# Puzzle_4-Digit_Display_V1_0.net
KiCad netlist of a schematic drawn in EAGLE
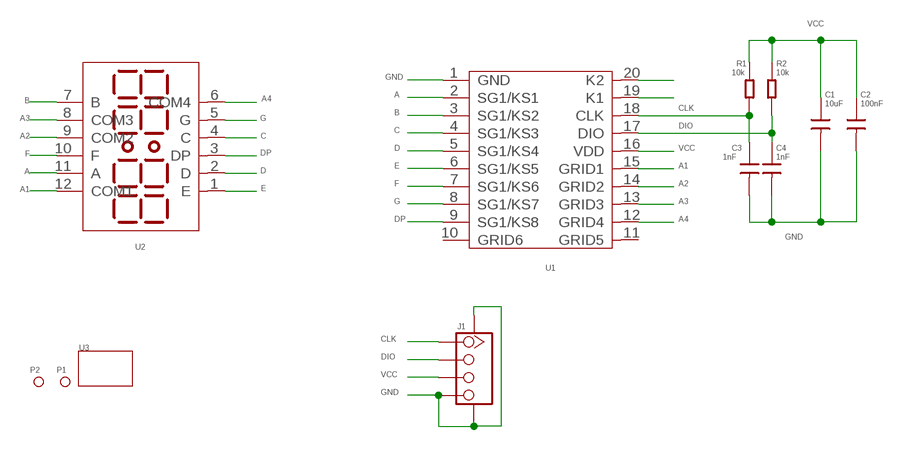
[diagram p0: schematic, sheet 1]

(export (version "E")
  (design (tool "Eeschema 10.0.6"))
  (components
    (comp (ref "C1")
      (value "10uF")
      (footprint "eagle-import:0603")
      (libsource (lib "eagle-import") (part "C-0603"))
    )
    (comp (ref "C2")
      (value "100nF")
      (footprint "eagle-import:0603")
      (libsource (lib "eagle-import") (part "C-0603"))
    )
    (comp (ref "C3")
      (value "1nF")
      (footprint "eagle-import:0603")
      (libsource (lib "eagle-import") (part "C-0603"))
    )
    (comp (ref "C4")
      (value "1nF")
      (footprint "eagle-import:0603")
      (libsource (lib "eagle-import") (part "C-0603"))
    )
    (comp (ref "J1")
      (value "TWIG-4P-2.0-SMD-FEMALE-REINFORCE'90D'")
      (footprint "eagle-import:4P-SMD-2.0-90D")
      (libsource (lib "eagle-import") (part "TWIG-4P-2.0-SMD-FEMALE-REINFORCE'90D'"))
    )
    (comp (ref "P1")
      (value "PAD-MARK")
      (footprint "eagle-import:ROUND-MARK-0.635")
      (libsource (lib "eagle-import") (part "PAD-MARK"))
    )
    (comp (ref "P2")
      (value "PAD-MARK")
      (footprint "eagle-import:ROUND-MARK-0.635")
      (libsource (lib "eagle-import") (part "PAD-MARK"))
    )
    (comp (ref "R1")
      (value "10k")
      (footprint "eagle-import:0603")
      (libsource (lib "eagle-import") (part "R-0603"))
    )
    (comp (ref "R2")
      (value "10k")
      (footprint "eagle-import:0603")
      (libsource (lib "eagle-import") (part "R-0603"))
    )
    (comp (ref "U1")
      (value "TM1637")
      (footprint "eagle-import:SOP20-10.45")
      (libsource (lib "eagle-import") (part "TM1637"))
    )
    (comp (ref "U2")
      (value "LED-4-BETY-7-SEG")
      (footprint "eagle-import:7-4-BYTE-SEG-2.54-30X14X7.3H")
      (libsource (lib "eagle-import") (part "LED-4-BETY-7-SEG"))
    )
    (comp (ref "U3")
      (value "TWIG-2U")
      (footprint "eagle-import:2U-DIM-W_-DRILL")
      (libsource (lib "eagle-import") (part "TWIG-2U"))
    )
  )
  (nets
    (net (code "1") (name "/A") (class "Default")
      (node (ref "U1") (pin "2") (pinfunction "SG1/KS1_2") (pintype "bidirectional"))
      (node (ref "U2") (pin "11") (pinfunction "A_11") (pintype "bidirectional"))
    )
    (net (code "2") (name "/A1") (class "Default")
      (node (ref "U1") (pin "15") (pinfunction "GRID1_15") (pintype "bidirectional"))
      (node (ref "U2") (pin "12") (pinfunction "COM1_12") (pintype "bidirectional"))
    )
    (net (code "3") (name "/A2") (class "Default")
      (node (ref "U1") (pin "14") (pinfunction "GRID2_14") (pintype "bidirectional"))
      (node (ref "U2") (pin "9") (pinfunction "COM2_9") (pintype "bidirectional"))
    )
    (net (code "4") (name "/A3") (class "Default")
      (node (ref "U1") (pin "13") (pinfunction "GRID3_13") (pintype "bidirectional"))
      (node (ref "U2") (pin "8") (pinfunction "COM3_8") (pintype "bidirectional"))
    )
    (net (code "5") (name "/A4") (class "Default")
      (node (ref "U1") (pin "12") (pinfunction "GRID4_12") (pintype "bidirectional"))
      (node (ref "U2") (pin "6") (pinfunction "COM4_6") (pintype "bidirectional"))
    )
    (net (code "6") (name "/B") (class "Default")
      (node (ref "U1") (pin "3") (pinfunction "SG1/KS2_3") (pintype "bidirectional"))
      (node (ref "U2") (pin "7") (pinfunction "B_7") (pintype "bidirectional"))
    )
    (net (code "7") (name "/C") (class "Default")
      (node (ref "U1") (pin "4") (pinfunction "SG1/KS3_4") (pintype "bidirectional"))
      (node (ref "U2") (pin "4") (pinfunction "C_4") (pintype "bidirectional"))
    )
    (net (code "8") (name "/CLK") (class "Default")
      (node (ref "C3") (pin "1") (pinfunction "1_1") (pintype "passive"))
      (node (ref "J1") (pin "1") (pinfunction "1_1") (pintype "bidirectional"))
      (node (ref "R1") (pin "2") (pinfunction "2_2") (pintype "passive"))
      (node (ref "U1") (pin "18") (pinfunction "CLK_18") (pintype "bidirectional"))
    )
    (net (code "9") (name "/D") (class "Default")
      (node (ref "U1") (pin "5") (pinfunction "SG1/KS4_5") (pintype "bidirectional"))
      (node (ref "U2") (pin "2") (pinfunction "D_2") (pintype "bidirectional"))
    )
    (net (code "10") (name "/DIO") (class "Default")
      (node (ref "C4") (pin "1") (pinfunction "1_1") (pintype "passive"))
      (node (ref "J1") (pin "2") (pinfunction "2_2") (pintype "bidirectional"))
      (node (ref "R2") (pin "2") (pinfunction "2_2") (pintype "passive"))
      (node (ref "U1") (pin "17") (pinfunction "DIO_17") (pintype "bidirectional"))
    )
    (net (code "11") (name "/DP") (class "Default")
      (node (ref "U1") (pin "9") (pinfunction "SG1/KS8_9") (pintype "bidirectional"))
      (node (ref "U2") (pin "3") (pinfunction "DP_3") (pintype "bidirectional"))
    )
    (net (code "12") (name "/E") (class "Default")
      (node (ref "U1") (pin "6") (pinfunction "SG1/KS5_6") (pintype "bidirectional"))
      (node (ref "U2") (pin "1") (pinfunction "E_1") (pintype "bidirectional"))
    )
    (net (code "13") (name "/F") (class "Default")
      (node (ref "U1") (pin "7") (pinfunction "SG1/KS6_7") (pintype "bidirectional"))
      (node (ref "U2") (pin "10") (pinfunction "F_10") (pintype "bidirectional"))
    )
    (net (code "14") (name "/G") (class "Default")
      (node (ref "U1") (pin "8") (pinfunction "SG1/KS7_8") (pintype "bidirectional"))
      (node (ref "U2") (pin "5") (pinfunction "G_5") (pintype "bidirectional"))
    )
    (net (code "15") (name "/GND") (class "Default")
      (node (ref "C1") (pin "2") (pinfunction "2_2") (pintype "passive"))
      (node (ref "C2") (pin "2") (pinfunction "2_2") (pintype "passive"))
      (node (ref "C3") (pin "2") (pinfunction "2_2") (pintype "passive"))
      (node (ref "C4") (pin "2") (pinfunction "2_2") (pintype "passive"))
      (node (ref "J1") (pin "4") (pinfunction "4_4") (pintype "bidirectional"))
      (node (ref "J1") (pin "SS1") (pinfunction "SS1_SS1") (pintype "bidirectional"))
      (node (ref "J1") (pin "SS2") (pinfunction "SS2_SS2") (pintype "bidirectional"))
      (node (ref "U1") (pin "1") (pinfunction "GND_1") (pintype "bidirectional"))
    )
    (net (code "16") (name "/VCC") (class "Default")
      (node (ref "C1") (pin "1") (pinfunction "1_1") (pintype "passive"))
      (node (ref "C2") (pin "1") (pinfunction "1_1") (pintype "passive"))
      (node (ref "J1") (pin "3") (pinfunction "3_3") (pintype "bidirectional"))
      (node (ref "R1") (pin "1") (pinfunction "1_1") (pintype "passive"))
      (node (ref "R2") (pin "1") (pinfunction "1_1") (pintype "passive"))
      (node (ref "U1") (pin "16") (pinfunction "VDD_16") (pintype "bidirectional"))
    )
    (net (code "17") (name "unconnected-(U1-GRID5-Pad11)") (class "Default")
      (node (ref "U1") (pin "11") (pinfunction "GRID5_11") (pintype "bidirectional"))
    )
    (net (code "18") (name "unconnected-(U1-GRID6-Pad10)") (class "Default")
      (node (ref "U1") (pin "10") (pinfunction "GRID6_10") (pintype "bidirectional"))
    )
    (net (code "19") (name "unconnected-(U1-K1-Pad19)") (class "Default")
      (node (ref "U1") (pin "19") (pinfunction "K1_19") (pintype "bidirectional"))
    )
    (net (code "20") (name "unconnected-(U1-K2-Pad20)") (class "Default")
      (node (ref "U1") (pin "20") (pinfunction "K2_20") (pintype "bidirectional"))
    )
  )
)
